# rcstick-f-pico.net
KiCad netlist of a schematic drawn in EAGLE
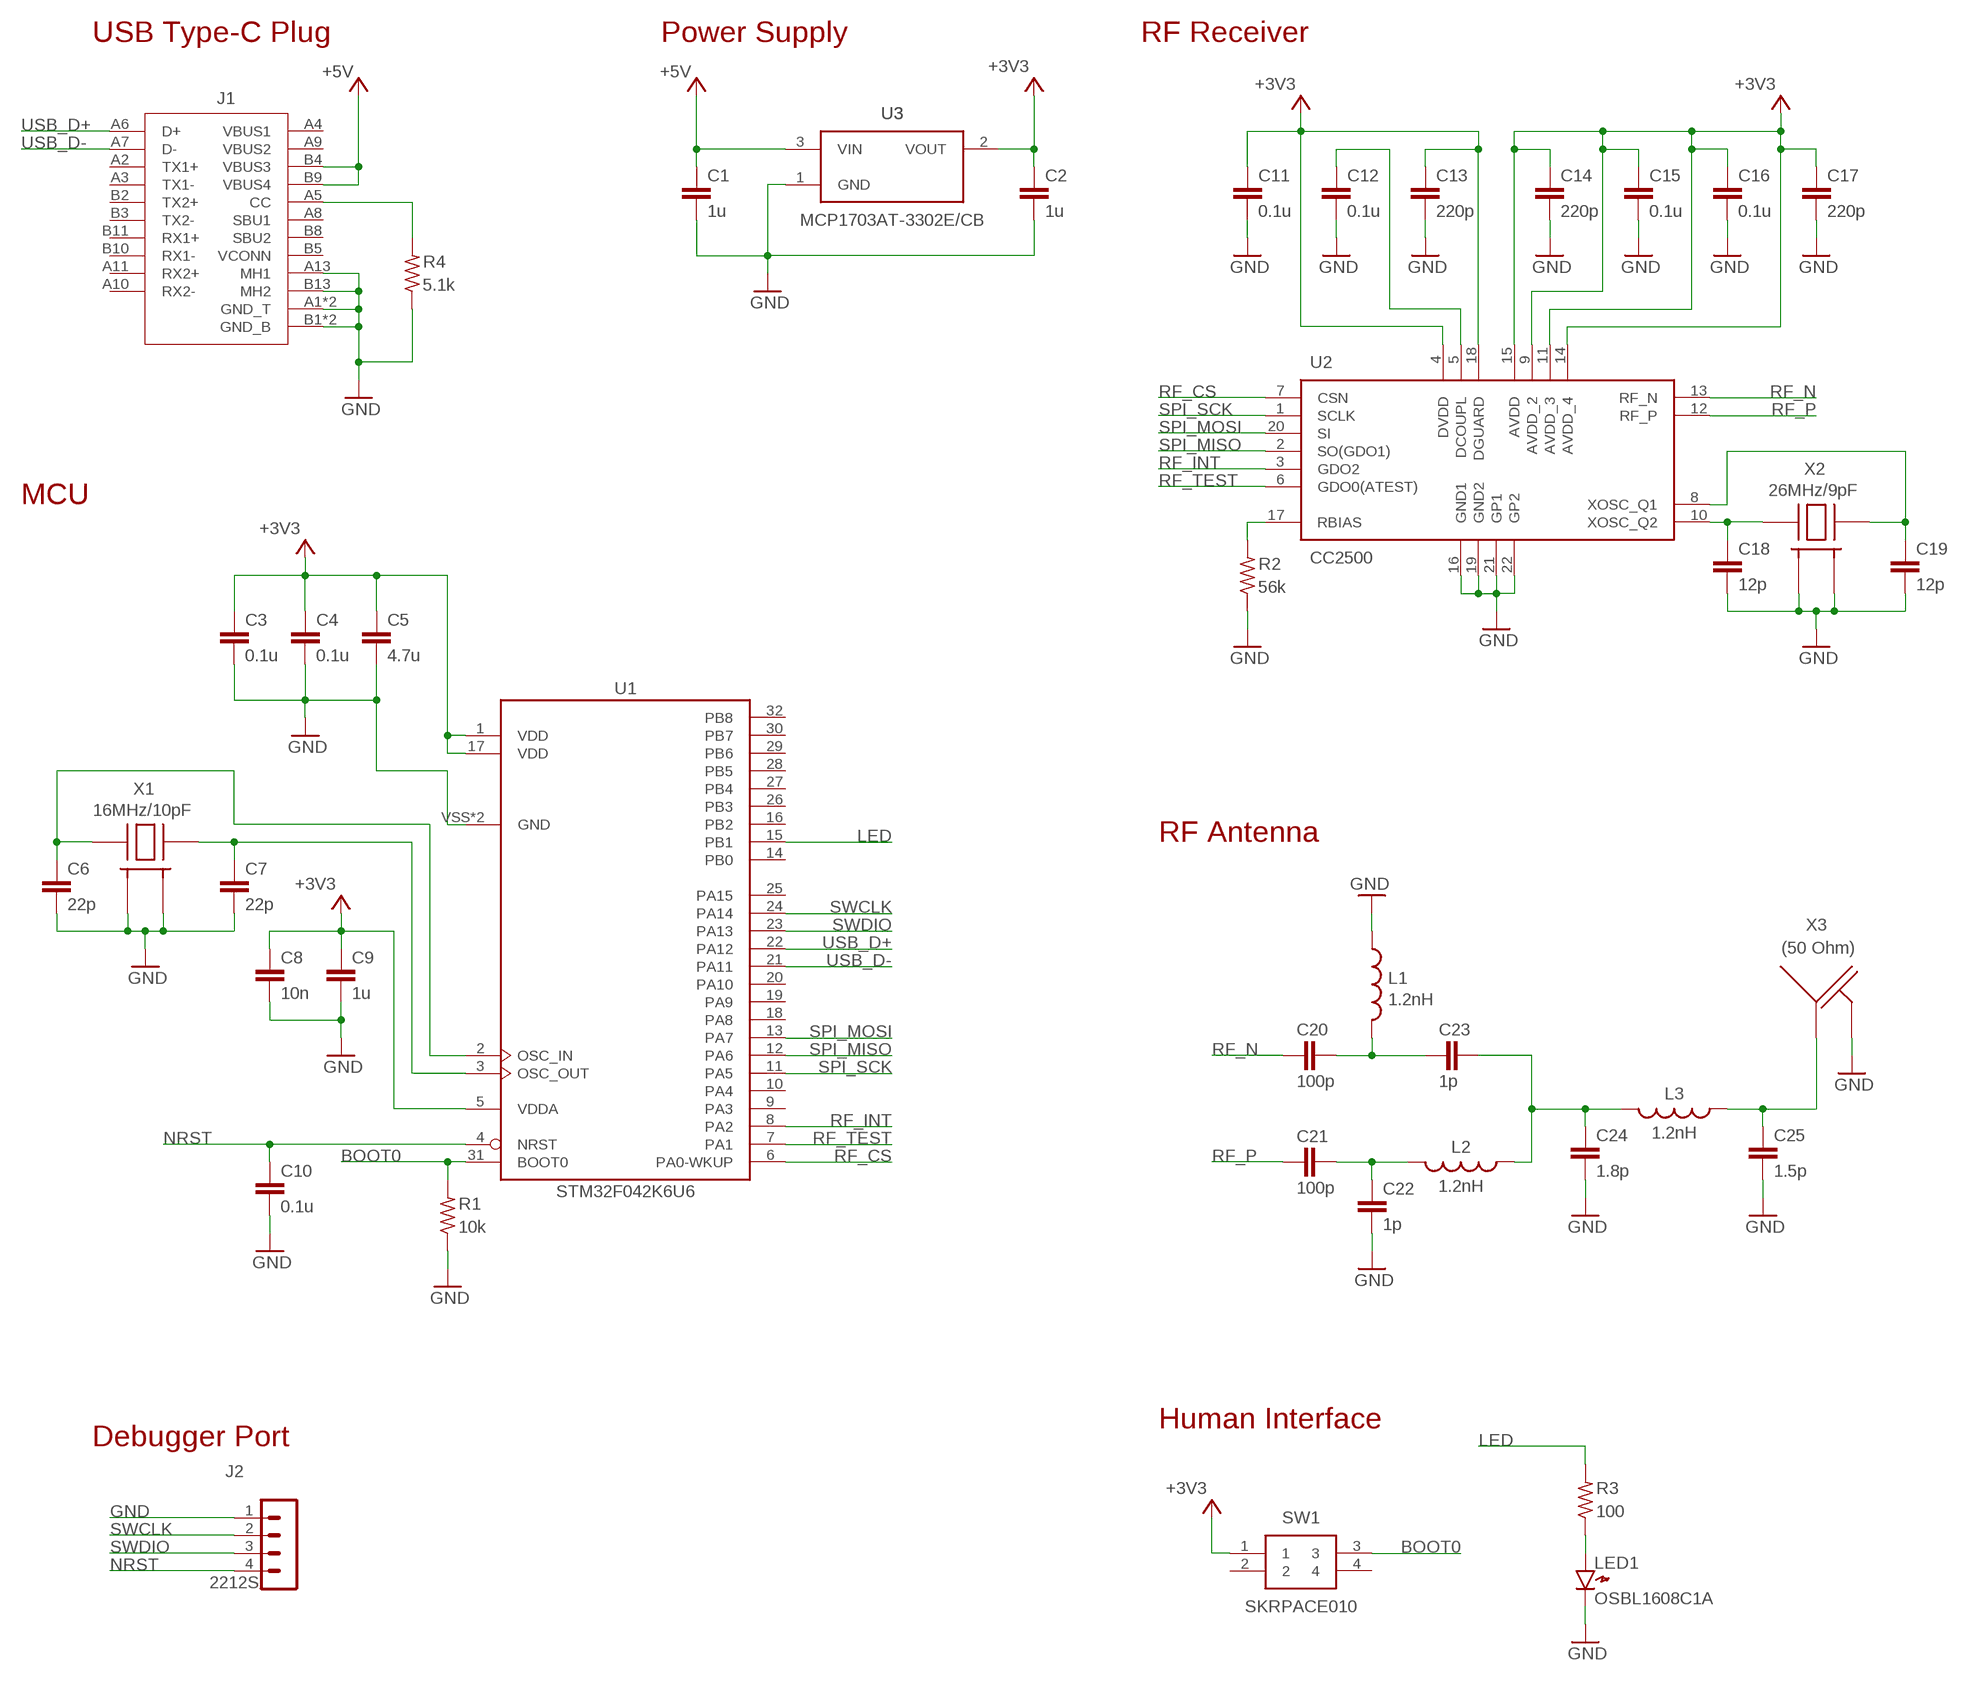
[diagram p0: schematic, sheet 1]

(export (version "E")
  (design (tool "Eeschema 10.0.6"))
  (components
    (comp (ref "C1")
      (value "1u")
      (footprint "eagle-import:RCL_C0402_HS")
      (libsource (lib "eagle-import") (part "RCL_C-EUC0402-HS"))
    )
    (comp (ref "C2")
      (value "1u")
      (footprint "eagle-import:RCL_C0402_HS")
      (libsource (lib "eagle-import") (part "RCL_C-EUC0402-HS"))
    )
    (comp (ref "C3")
      (value "0.1u")
      (footprint "eagle-import:RCL_C0402_HS")
      (libsource (lib "eagle-import") (part "RCL_C-EUC0402-HS"))
    )
    (comp (ref "C4")
      (value "0.1u")
      (footprint "eagle-import:RCL_C0402_HS")
      (libsource (lib "eagle-import") (part "RCL_C-EUC0402-HS"))
    )
    (comp (ref "C5")
      (value "4.7u")
      (footprint "eagle-import:RCL_C0402_HS")
      (libsource (lib "eagle-import") (part "RCL_C-EUC0402-HS"))
    )
    (comp (ref "C6")
      (value "22p")
      (footprint "eagle-import:RCL_C0402_HS")
      (libsource (lib "eagle-import") (part "RCL_C-EUC0402-HS"))
    )
    (comp (ref "C7")
      (value "22p")
      (footprint "eagle-import:RCL_C0402_HS")
      (libsource (lib "eagle-import") (part "RCL_C-EUC0402-HS"))
    )
    (comp (ref "C8")
      (value "10n")
      (footprint "eagle-import:RCL_C0402_HS")
      (libsource (lib "eagle-import") (part "RCL_C-EUC0402-HS"))
    )
    (comp (ref "C9")
      (value "1u")
      (footprint "eagle-import:RCL_C0402_HS")
      (libsource (lib "eagle-import") (part "RCL_C-EUC0402-HS"))
    )
    (comp (ref "C10")
      (value "0.1u")
      (footprint "eagle-import:RCL_C0402_HS")
      (libsource (lib "eagle-import") (part "RCL_C-EUC0402-HS"))
    )
    (comp (ref "C11")
      (value "0.1u")
      (footprint "eagle-import:RCL_C0402_HS")
      (libsource (lib "eagle-import") (part "RCL_C-EUC0402-HS"))
    )
    (comp (ref "C12")
      (value "0.1u")
      (footprint "eagle-import:RCL_C0402_HS")
      (libsource (lib "eagle-import") (part "RCL_C-EUC0402-HS"))
    )
    (comp (ref "C13")
      (value "220p")
      (footprint "eagle-import:RCL_C0402_HS")
      (libsource (lib "eagle-import") (part "RCL_C-EUC0402-HS"))
    )
    (comp (ref "C14")
      (value "220p")
      (footprint "eagle-import:RCL_C0402_HS")
      (libsource (lib "eagle-import") (part "RCL_C-EUC0402-HS"))
    )
    (comp (ref "C15")
      (value "0.1u")
      (footprint "eagle-import:RCL_C0402_HS")
      (libsource (lib "eagle-import") (part "RCL_C-EUC0402-HS"))
    )
    (comp (ref "C16")
      (value "0.1u")
      (footprint "eagle-import:RCL_C0402_HS")
      (libsource (lib "eagle-import") (part "RCL_C-EUC0402-HS"))
    )
    (comp (ref "C17")
      (value "220p")
      (footprint "eagle-import:RCL_C0402_HS")
      (libsource (lib "eagle-import") (part "RCL_C-EUC0402-HS"))
    )
    (comp (ref "C18")
      (value "12p")
      (footprint "eagle-import:RCL_C0402_HS")
      (libsource (lib "eagle-import") (part "RCL_C-EUC0402-HS"))
    )
    (comp (ref "C19")
      (value "12p")
      (footprint "eagle-import:RCL_C0402_HS")
      (libsource (lib "eagle-import") (part "RCL_C-EUC0402-HS"))
    )
    (comp (ref "C20")
      (value "100p")
      (footprint "eagle-import:RCL_C0402_HS")
      (libsource (lib "eagle-import") (part "RCL_C-EUC0402-HS"))
    )
    (comp (ref "C21")
      (value "100p")
      (footprint "eagle-import:RCL_C0402_HS")
      (libsource (lib "eagle-import") (part "RCL_C-EUC0402-HS"))
    )
    (comp (ref "C22")
      (value "1p")
      (footprint "eagle-import:RCL_C0402_HS")
      (libsource (lib "eagle-import") (part "RCL_C-EUC0402-HS"))
    )
    (comp (ref "C23")
      (value "1p")
      (footprint "eagle-import:RCL_C0402_HS")
      (libsource (lib "eagle-import") (part "RCL_C-EUC0402-HS"))
    )
    (comp (ref "C24")
      (value "1.8p")
      (footprint "eagle-import:RCL_C0402_HS")
      (libsource (lib "eagle-import") (part "RCL_C-EUC0402-HS"))
    )
    (comp (ref "C25")
      (value "1.5p")
      (footprint "eagle-import:RCL_C0402_HS")
      (libsource (lib "eagle-import") (part "RCL_C-EUC0402-HS"))
    )
    (comp (ref "J1")
      (value "USB-TYPEC-1054440001-HS")
      (footprint "eagle-import:USB-TYPEC-1054440001-HS")
      (libsource (lib "eagle-import") (part "USB-TYPEC-1054440001-HS"))
    )
    (comp (ref "J2")
      (value "2212S")
      (footprint "eagle-import:53047-0410")
      (libsource (lib "eagle-import") (part "53047-0410"))
    )
    (comp (ref "L1")
      (value "1.2nH")
      (footprint "eagle-import:RCL_L0402_HS")
      (libsource (lib "eagle-import") (part "RCL_L-USL0402-HS"))
    )
    (comp (ref "L2")
      (value "1.2nH")
      (footprint "eagle-import:RCL_L0402_HS")
      (libsource (lib "eagle-import") (part "RCL_L-USL0402-HS"))
    )
    (comp (ref "L3")
      (value "1.2nH")
      (footprint "eagle-import:RCL_L0402_HS")
      (libsource (lib "eagle-import") (part "RCL_L-USL0402-HS"))
    )
    (comp (ref "LED1")
      (value "OSBL1608C1A")
      (footprint "eagle-import:LED1608")
      (libsource (lib "eagle-import") (part "LED1608"))
    )
    (comp (ref "R1")
      (value "10k")
      (footprint "eagle-import:RCL_R0402_HS")
      (libsource (lib "eagle-import") (part "RCL_R-US_R0402-HS"))
    )
    (comp (ref "R2")
      (value "56k")
      (footprint "eagle-import:RCL_R0402_HS")
      (libsource (lib "eagle-import") (part "RCL_R-US_R0402-HS"))
    )
    (comp (ref "R3")
      (value "100")
      (footprint "eagle-import:RCL_R0402_HS")
      (libsource (lib "eagle-import") (part "RCL_R-US_R0402-HS"))
    )
    (comp (ref "R4")
      (value "5.1k")
      (footprint "eagle-import:RCL_R0402_HS")
      (libsource (lib "eagle-import") (part "RCL_R-US_R0402-HS"))
    )
    (comp (ref "SW1")
      (value "SKRPACE010")
      (footprint "eagle-import:SMT(4.2X3.2)")
      (libsource (lib "eagle-import") (part "SKRPACE010"))
    )
    (comp (ref "U1")
      (value "STM32F042K6U6")
      (footprint "eagle-import:UQFPN32-M")
      (libsource (lib "eagle-import") (part "STM32F042K6U-M"))
    )
    (comp (ref "U2")
      (value "CC2500")
      (footprint "eagle-import:CC2500-RTY1_CC2500-HS")
      (libsource (lib "eagle-import") (part "CC2500-HS"))
    )
    (comp (ref "U3")
      (value "MCP1703AT-3302E/CB")
      (footprint "eagle-import:SOT23")
      (libsource (lib "eagle-import") (part "LDO-REGULATOR"))
    )
    (comp (ref "X1")
      (value "16MHz/10pF")
      (footprint "eagle-import:CRYSTAL3225-HS")
      (libsource (lib "eagle-import") (part "CRYSTAL3225HS"))
    )
    (comp (ref "X2")
      (value "26MHz/9pF")
      (footprint "eagle-import:CRYSTAL3225-HS")
      (libsource (lib "eagle-import") (part "CRYSTAL3225HS"))
    )
    (comp (ref "X3")
      (value "(50 Ohm)")
      (footprint "eagle-import:2.4GHZ-INVERTED-F-SMALL-FLIP")
      (libsource (lib "eagle-import") (part "2.4GHZ-INVERED-FSMALL-FLIP"))
    )
  )
  (nets
    (net (code "1") (name "+3V3") (class "Default")
      (node (ref "C11") (pin "1") (pinfunction "1_1") (pintype "passive"))
      (node (ref "C13") (pin "1") (pinfunction "1_1") (pintype "passive"))
      (node (ref "C14") (pin "1") (pinfunction "1_1") (pintype "passive"))
      (node (ref "C15") (pin "1") (pinfunction "1_1") (pintype "passive"))
      (node (ref "C16") (pin "1") (pinfunction "1_1") (pintype "passive"))
      (node (ref "C17") (pin "1") (pinfunction "1_1") (pintype "passive"))
      (node (ref "C2") (pin "1") (pinfunction "1_1") (pintype "passive"))
      (node (ref "C3") (pin "1") (pinfunction "1_1") (pintype "passive"))
      (node (ref "C4") (pin "1") (pinfunction "1_1") (pintype "passive"))
      (node (ref "C5") (pin "1") (pinfunction "1_1") (pintype "passive"))
      (node (ref "C8") (pin "1") (pinfunction "1_1") (pintype "passive"))
      (node (ref "C9") (pin "1") (pinfunction "1_1") (pintype "passive"))
      (node (ref "SW1") (pin "1") (pinfunction "1_1") (pintype "bidirectional"))
      (node (ref "U1") (pin "1") (pinfunction "VDD_1") (pintype "power_in"))
      (node (ref "U1") (pin "17") (pinfunction "VDD_17") (pintype "power_in"))
      (node (ref "U1") (pin "5") (pinfunction "VDDA_5") (pintype "power_in"))
      (node (ref "U2") (pin "11") (pinfunction "AVDD_3_11") (pintype "bidirectional"))
      (node (ref "U2") (pin "14") (pinfunction "AVDD_4_14") (pintype "bidirectional"))
      (node (ref "U2") (pin "15") (pinfunction "AVDD_15") (pintype "bidirectional"))
      (node (ref "U2") (pin "18") (pinfunction "DGUARD_18") (pintype "bidirectional"))
      (node (ref "U2") (pin "4") (pinfunction "DVDD_4") (pintype "bidirectional"))
      (node (ref "U2") (pin "9") (pinfunction "AVDD_2_9") (pintype "bidirectional"))
      (node (ref "U3") (pin "2") (pinfunction "VOUT_2") (pintype "bidirectional"))
    )
    (net (code "2") (name "+5V") (class "Default")
      (node (ref "C1") (pin "1") (pinfunction "1_1") (pintype "passive"))
      (node (ref "J1") (pin "B4") (pinfunction "VBUS3_B4") (pintype "bidirectional"))
      (node (ref "J1") (pin "B9") (pinfunction "VBUS4_B9") (pintype "bidirectional"))
      (node (ref "U3") (pin "3") (pinfunction "VIN_3") (pintype "bidirectional"))
    )
    (net (code "3") (name "/BOOT0") (class "Default")
      (node (ref "R1") (pin "2") (pinfunction "2_2") (pintype "passive"))
      (node (ref "SW1") (pin "3") (pinfunction "3_3") (pintype "bidirectional"))
      (node (ref "U1") (pin "31") (pinfunction "BOOT0_31") (pintype "input"))
    )
    (net (code "4") (name "/LED") (class "Default")
      (node (ref "R3") (pin "2") (pinfunction "2_2") (pintype "passive"))
      (node (ref "U1") (pin "15") (pinfunction "PB1_15") (pintype "bidirectional"))
    )
    (net (code "5") (name "/NRST") (class "Default")
      (node (ref "C10") (pin "1") (pinfunction "1_1") (pintype "passive"))
      (node (ref "J2") (pin "4") (pinfunction "4_4") (pintype "passive"))
      (node (ref "U1") (pin "4") (pinfunction "NRST_4") (pintype "bidirectional"))
    )
    (net (code "6") (name "/RF_CS") (class "Default")
      (node (ref "U1") (pin "6") (pinfunction "PA0-WKUP_6") (pintype "bidirectional"))
      (node (ref "U2") (pin "7") (pinfunction "CSN_7") (pintype "bidirectional"))
    )
    (net (code "7") (name "/RF_INT") (class "Default")
      (node (ref "U1") (pin "8") (pinfunction "PA2_8") (pintype "bidirectional"))
      (node (ref "U2") (pin "3") (pinfunction "GDO2_3") (pintype "bidirectional"))
    )
    (net (code "8") (name "/RF_N") (class "Default")
      (node (ref "C20") (pin "1") (pinfunction "1_1") (pintype "passive"))
      (node (ref "U2") (pin "13") (pinfunction "RF_N_13") (pintype "bidirectional"))
    )
    (net (code "9") (name "/RF_P") (class "Default")
      (node (ref "C21") (pin "1") (pinfunction "1_1") (pintype "passive"))
      (node (ref "U2") (pin "12") (pinfunction "RF_P_12") (pintype "bidirectional"))
    )
    (net (code "10") (name "/RF_TEST") (class "Default")
      (node (ref "U1") (pin "7") (pinfunction "PA1_7") (pintype "bidirectional"))
      (node (ref "U2") (pin "6") (pinfunction "GDO0(ATEST)_6") (pintype "bidirectional"))
    )
    (net (code "11") (name "/SPI_MISO") (class "Default")
      (node (ref "U1") (pin "12") (pinfunction "PA6_12") (pintype "bidirectional"))
      (node (ref "U2") (pin "2") (pinfunction "SO(GDO1)_2") (pintype "bidirectional"))
    )
    (net (code "12") (name "/SPI_MOSI") (class "Default")
      (node (ref "U1") (pin "13") (pinfunction "PA7_13") (pintype "bidirectional"))
      (node (ref "U2") (pin "20") (pinfunction "SI_20") (pintype "bidirectional"))
    )
    (net (code "13") (name "/SPI_SCK") (class "Default")
      (node (ref "U1") (pin "11") (pinfunction "PA5_11") (pintype "bidirectional"))
      (node (ref "U2") (pin "1") (pinfunction "SCLK_1") (pintype "bidirectional"))
    )
    (net (code "14") (name "/SWCLK") (class "Default")
      (node (ref "J2") (pin "2") (pinfunction "2_2") (pintype "passive"))
      (node (ref "U1") (pin "24") (pinfunction "PA14_24") (pintype "bidirectional"))
    )
    (net (code "15") (name "/SWDIO") (class "Default")
      (node (ref "J2") (pin "3") (pinfunction "3_3") (pintype "passive"))
      (node (ref "U1") (pin "23") (pinfunction "PA13_23") (pintype "bidirectional"))
    )
    (net (code "16") (name "/USB_D+") (class "Default")
      (node (ref "J1") (pin "A6") (pinfunction "D+_A6") (pintype "bidirectional"))
      (node (ref "U1") (pin "22") (pinfunction "PA12_22") (pintype "bidirectional"))
    )
    (net (code "17") (name "/USB_D-") (class "Default")
      (node (ref "J1") (pin "A7") (pinfunction "D-_A7") (pintype "bidirectional"))
      (node (ref "U1") (pin "21") (pinfunction "PA11_21") (pintype "bidirectional"))
    )
    (net (code "18") (name "GND") (class "Default")
      (node (ref "C1") (pin "2") (pinfunction "2_2") (pintype "passive"))
      (node (ref "C10") (pin "2") (pinfunction "2_2") (pintype "passive"))
      (node (ref "C11") (pin "2") (pinfunction "2_2") (pintype "passive"))
      (node (ref "C12") (pin "2") (pinfunction "2_2") (pintype "passive"))
      (node (ref "C13") (pin "2") (pinfunction "2_2") (pintype "passive"))
      (node (ref "C14") (pin "2") (pinfunction "2_2") (pintype "passive"))
      (node (ref "C15") (pin "2") (pinfunction "2_2") (pintype "passive"))
      (node (ref "C16") (pin "2") (pinfunction "2_2") (pintype "passive"))
      (node (ref "C17") (pin "2") (pinfunction "2_2") (pintype "passive"))
      (node (ref "C18") (pin "2") (pinfunction "2_2") (pintype "passive"))
      (node (ref "C19") (pin "2") (pinfunction "2_2") (pintype "passive"))
      (node (ref "C2") (pin "2") (pinfunction "2_2") (pintype "passive"))
      (node (ref "C22") (pin "2") (pinfunction "2_2") (pintype "passive"))
      (node (ref "C24") (pin "2") (pinfunction "2_2") (pintype "passive"))
      (node (ref "C25") (pin "2") (pinfunction "2_2") (pintype "passive"))
      (node (ref "C3") (pin "2") (pinfunction "2_2") (pintype "passive"))
      (node (ref "C4") (pin "2") (pinfunction "2_2") (pintype "passive"))
      (node (ref "C5") (pin "2") (pinfunction "2_2") (pintype "passive"))
      (node (ref "C6") (pin "2") (pinfunction "2_2") (pintype "passive"))
      (node (ref "C7") (pin "2") (pinfunction "2_2") (pintype "passive"))
      (node (ref "C8") (pin "2") (pinfunction "2_2") (pintype "passive"))
      (node (ref "C9") (pin "2") (pinfunction "2_2") (pintype "passive"))
      (node (ref "J1") (pin "A1") (pinfunction "GND_T_A1") (pintype "bidirectional"))
      (node (ref "J1") (pin "A12") (pinfunction "GND_T_A12") (pintype "bidirectional"))
      (node (ref "J1") (pin "A13") (pinfunction "MH1_A13") (pintype "bidirectional"))
      (node (ref "J1") (pin "B1") (pinfunction "GND_B_B1") (pintype "bidirectional"))
      (node (ref "J1") (pin "B12") (pinfunction "GND_B_B12") (pintype "bidirectional"))
      (node (ref "J1") (pin "B13") (pinfunction "MH2_B13") (pintype "bidirectional"))
      (node (ref "J2") (pin "1") (pinfunction "1_1") (pintype "passive"))
      (node (ref "L1") (pin "1") (pinfunction "1_1") (pintype "passive"))
      (node (ref "LED1") (pin "K") (pinfunction "K_K") (pintype "passive"))
      (node (ref "R1") (pin "1") (pinfunction "1_1") (pintype "passive"))
      (node (ref "R2") (pin "1") (pinfunction "1_1") (pintype "passive"))
      (node (ref "R4") (pin "1") (pinfunction "1_1") (pintype "passive"))
      (node (ref "U1") (pin "VSS") (pinfunction "GND_VSS") (pintype "power_in"))
      (node (ref "U1") (pin "VSSH") (pinfunction "GND_VSSH") (pintype "power_in"))
      (node (ref "U2") (pin "16") (pinfunction "GND1_16") (pintype "bidirectional"))
      (node (ref "U2") (pin "19") (pinfunction "GND2_19") (pintype "bidirectional"))
      (node (ref "U2") (pin "21") (pinfunction "GP1_21") (pintype "bidirectional"))
      (node (ref "U2") (pin "22") (pinfunction "GP2_22") (pintype "bidirectional"))
      (node (ref "U3") (pin "1") (pinfunction "GND_1") (pintype "bidirectional"))
      (node (ref "X1") (pin "2") (pinfunction "GND_1_2") (pintype "bidirectional"))
      (node (ref "X1") (pin "4") (pinfunction "GND_2_4") (pintype "bidirectional"))
      (node (ref "X2") (pin "2") (pinfunction "GND_1_2") (pintype "bidirectional"))
      (node (ref "X2") (pin "4") (pinfunction "GND_2_4") (pintype "bidirectional"))
      (node (ref "X3") (pin "2") (pinfunction "GND_2") (pintype "bidirectional"))
    )
    (net (code "19") (name "Net-(C20-Pad2)") (class "Default")
      (node (ref "C20") (pin "2") (pinfunction "2_2") (pintype "passive"))
      (node (ref "C23") (pin "1") (pinfunction "1_1") (pintype "passive"))
      (node (ref "L1") (pin "2") (pinfunction "2_2") (pintype "passive"))
    )
    (net (code "20") (name "Net-(C21-Pad2)") (class "Default")
      (node (ref "C21") (pin "2") (pinfunction "2_2") (pintype "passive"))
      (node (ref "C22") (pin "1") (pinfunction "1_1") (pintype "passive"))
      (node (ref "L2") (pin "2") (pinfunction "2_2") (pintype "passive"))
    )
    (net (code "21") (name "Net-(C23-Pad2)") (class "Default")
      (node (ref "C23") (pin "2") (pinfunction "2_2") (pintype "passive"))
      (node (ref "C24") (pin "1") (pinfunction "1_1") (pintype "passive"))
      (node (ref "L2") (pin "1") (pinfunction "1_1") (pintype "passive"))
      (node (ref "L3") (pin "2") (pinfunction "2_2") (pintype "passive"))
    )
    (net (code "22") (name "Net-(J1-CC)") (class "Default")
      (node (ref "J1") (pin "A5") (pinfunction "CC_A5") (pintype "bidirectional"))
      (node (ref "R4") (pin "2") (pinfunction "2_2") (pintype "passive"))
    )
    (net (code "23") (name "Net-(LED1-PadA)") (class "Default")
      (node (ref "LED1") (pin "A") (pinfunction "A_A") (pintype "passive"))
      (node (ref "R3") (pin "1") (pinfunction "1_1") (pintype "passive"))
    )
    (net (code "24") (name "Net-(U1-OSC_IN)") (class "Default")
      (node (ref "C6") (pin "1") (pinfunction "1_1") (pintype "passive"))
      (node (ref "U1") (pin "2") (pinfunction "OSC_IN_2") (pintype "bidirectional"))
      (node (ref "X1") (pin "1") (pinfunction "HOT_1_1") (pintype "bidirectional"))
    )
    (net (code "25") (name "Net-(U1-OSC_OUT)") (class "Default")
      (node (ref "C7") (pin "1") (pinfunction "1_1") (pintype "passive"))
      (node (ref "U1") (pin "3") (pinfunction "OSC_OUT_3") (pintype "bidirectional"))
      (node (ref "X1") (pin "3") (pinfunction "HOT_2_3") (pintype "bidirectional"))
    )
    (net (code "26") (name "Net-(U2-DCOUPL)") (class "Default")
      (node (ref "C12") (pin "1") (pinfunction "1_1") (pintype "passive"))
      (node (ref "U2") (pin "5") (pinfunction "DCOUPL_5") (pintype "bidirectional"))
    )
    (net (code "27") (name "Net-(U2-RBIAS)") (class "Default")
      (node (ref "R2") (pin "2") (pinfunction "2_2") (pintype "passive"))
      (node (ref "U2") (pin "17") (pinfunction "RBIAS_17") (pintype "bidirectional"))
    )
    (net (code "28") (name "Net-(U2-XOSC_Q1)") (class "Default")
      (node (ref "C19") (pin "1") (pinfunction "1_1") (pintype "passive"))
      (node (ref "U2") (pin "8") (pinfunction "XOSC_Q1_8") (pintype "bidirectional"))
      (node (ref "X2") (pin "3") (pinfunction "HOT_2_3") (pintype "bidirectional"))
    )
    (net (code "29") (name "Net-(U2-XOSC_Q2)") (class "Default")
      (node (ref "C18") (pin "1") (pinfunction "1_1") (pintype "passive"))
      (node (ref "U2") (pin "10") (pinfunction "XOSC_Q2_10") (pintype "bidirectional"))
      (node (ref "X2") (pin "1") (pinfunction "HOT_1_1") (pintype "bidirectional"))
    )
    (net (code "30") (name "Net-(X3-ANT)") (class "Default")
      (node (ref "C25") (pin "1") (pinfunction "1_1") (pintype "passive"))
      (node (ref "L3") (pin "1") (pinfunction "1_1") (pintype "passive"))
      (node (ref "X3") (pin "1") (pinfunction "ANT_1") (pintype "bidirectional"))
    )
    (net (code "31") (name "unconnected-(J1-RX1+-PadB11)") (class "Default")
      (node (ref "J1") (pin "B11") (pinfunction "RX1+_B11") (pintype "bidirectional"))
    )
    (net (code "32") (name "unconnected-(J1-RX1--PadB10)") (class "Default")
      (node (ref "J1") (pin "B10") (pinfunction "RX1-_B10") (pintype "bidirectional"))
    )
    (net (code "33") (name "unconnected-(J1-RX2+-PadA11)") (class "Default")
      (node (ref "J1") (pin "A11") (pinfunction "RX2+_A11") (pintype "bidirectional"))
    )
    (net (code "34") (name "unconnected-(J1-RX2--PadA10)") (class "Default")
      (node (ref "J1") (pin "A10") (pinfunction "RX2-_A10") (pintype "bidirectional"))
    )
    (net (code "35") (name "unconnected-(J1-SBU1-PadA8)") (class "Default")
      (node (ref "J1") (pin "A8") (pinfunction "SBU1_A8") (pintype "bidirectional"))
    )
    (net (code "36") (name "unconnected-(J1-SBU2-PadB8)") (class "Default")
      (node (ref "J1") (pin "B8") (pinfunction "SBU2_B8") (pintype "bidirectional"))
    )
    (net (code "37") (name "unconnected-(J1-TX1+-PadA2)") (class "Default")
      (node (ref "J1") (pin "A2") (pinfunction "TX1+_A2") (pintype "bidirectional"))
    )
    (net (code "38") (name "unconnected-(J1-TX1--PadA3)") (class "Default")
      (node (ref "J1") (pin "A3") (pinfunction "TX1-_A3") (pintype "bidirectional"))
    )
    (net (code "39") (name "unconnected-(J1-TX2+-PadB2)") (class "Default")
      (node (ref "J1") (pin "B2") (pinfunction "TX2+_B2") (pintype "bidirectional"))
    )
    (net (code "40") (name "unconnected-(J1-TX2--PadB3)") (class "Default")
      (node (ref "J1") (pin "B3") (pinfunction "TX2-_B3") (pintype "bidirectional"))
    )
    (net (code "41") (name "unconnected-(J1-VBUS1-PadA4)") (class "Default")
      (node (ref "J1") (pin "A4") (pinfunction "VBUS1_A4") (pintype "bidirectional"))
    )
    (net (code "42") (name "unconnected-(J1-VBUS2-PadA9)") (class "Default")
      (node (ref "J1") (pin "A9") (pinfunction "VBUS2_A9") (pintype "bidirectional"))
    )
    (net (code "43") (name "unconnected-(J1-VCONN-PadB5)") (class "Default")
      (node (ref "J1") (pin "B5") (pinfunction "VCONN_B5") (pintype "bidirectional"))
    )
    (net (code "44") (name "unconnected-(SW1-Pad2)") (class "Default")
      (node (ref "SW1") (pin "2") (pinfunction "2_2") (pintype "bidirectional"))
    )
    (net (code "45") (name "unconnected-(SW1-Pad4)") (class "Default")
      (node (ref "SW1") (pin "4") (pinfunction "4_4") (pintype "bidirectional"))
    )
    (net (code "46") (name "unconnected-(U1-PA3-Pad9)") (class "Default")
      (node (ref "U1") (pin "9") (pinfunction "PA3_9") (pintype "bidirectional"))
    )
    (net (code "47") (name "unconnected-(U1-PA4-Pad10)") (class "Default")
      (node (ref "U1") (pin "10") (pinfunction "PA4_10") (pintype "bidirectional"))
    )
    (net (code "48") (name "unconnected-(U1-PA8-Pad18)") (class "Default")
      (node (ref "U1") (pin "18") (pinfunction "PA8_18") (pintype "bidirectional"))
    )
    (net (code "49") (name "unconnected-(U1-PA9-Pad19)") (class "Default")
      (node (ref "U1") (pin "19") (pinfunction "PA9_19") (pintype "bidirectional"))
    )
    (net (code "50") (name "unconnected-(U1-PA10-Pad20)") (class "Default")
      (node (ref "U1") (pin "20") (pinfunction "PA10_20") (pintype "bidirectional"))
    )
    (net (code "51") (name "unconnected-(U1-PA15-Pad25)") (class "Default")
      (node (ref "U1") (pin "25") (pinfunction "PA15_25") (pintype "bidirectional"))
    )
    (net (code "52") (name "unconnected-(U1-PB0-Pad14)") (class "Default")
      (node (ref "U1") (pin "14") (pinfunction "PB0_14") (pintype "bidirectional"))
    )
    (net (code "53") (name "unconnected-(U1-PB2-Pad16)") (class "Default")
      (node (ref "U1") (pin "16") (pinfunction "PB2_16") (pintype "bidirectional"))
    )
    (net (code "54") (name "unconnected-(U1-PB3-Pad26)") (class "Default")
      (node (ref "U1") (pin "26") (pinfunction "PB3_26") (pintype "bidirectional"))
    )
    (net (code "55") (name "unconnected-(U1-PB4-Pad27)") (class "Default")
      (node (ref "U1") (pin "27") (pinfunction "PB4_27") (pintype "bidirectional"))
    )
    (net (code "56") (name "unconnected-(U1-PB5-Pad28)") (class "Default")
      (node (ref "U1") (pin "28") (pinfunction "PB5_28") (pintype "bidirectional"))
    )
    (net (code "57") (name "unconnected-(U1-PB6-Pad29)") (class "Default")
      (node (ref "U1") (pin "29") (pinfunction "PB6_29") (pintype "bidirectional"))
    )
    (net (code "58") (name "unconnected-(U1-PB7-Pad30)") (class "Default")
      (node (ref "U1") (pin "30") (pinfunction "PB7_30") (pintype "bidirectional"))
    )
    (net (code "59") (name "unconnected-(U1-PB8-Pad32)") (class "Default")
      (node (ref "U1") (pin "32") (pinfunction "PB8_32") (pintype "bidirectional"))
    )
  )
)
